# 3.net
KiCad netlist of a schematic drawn in EAGLE
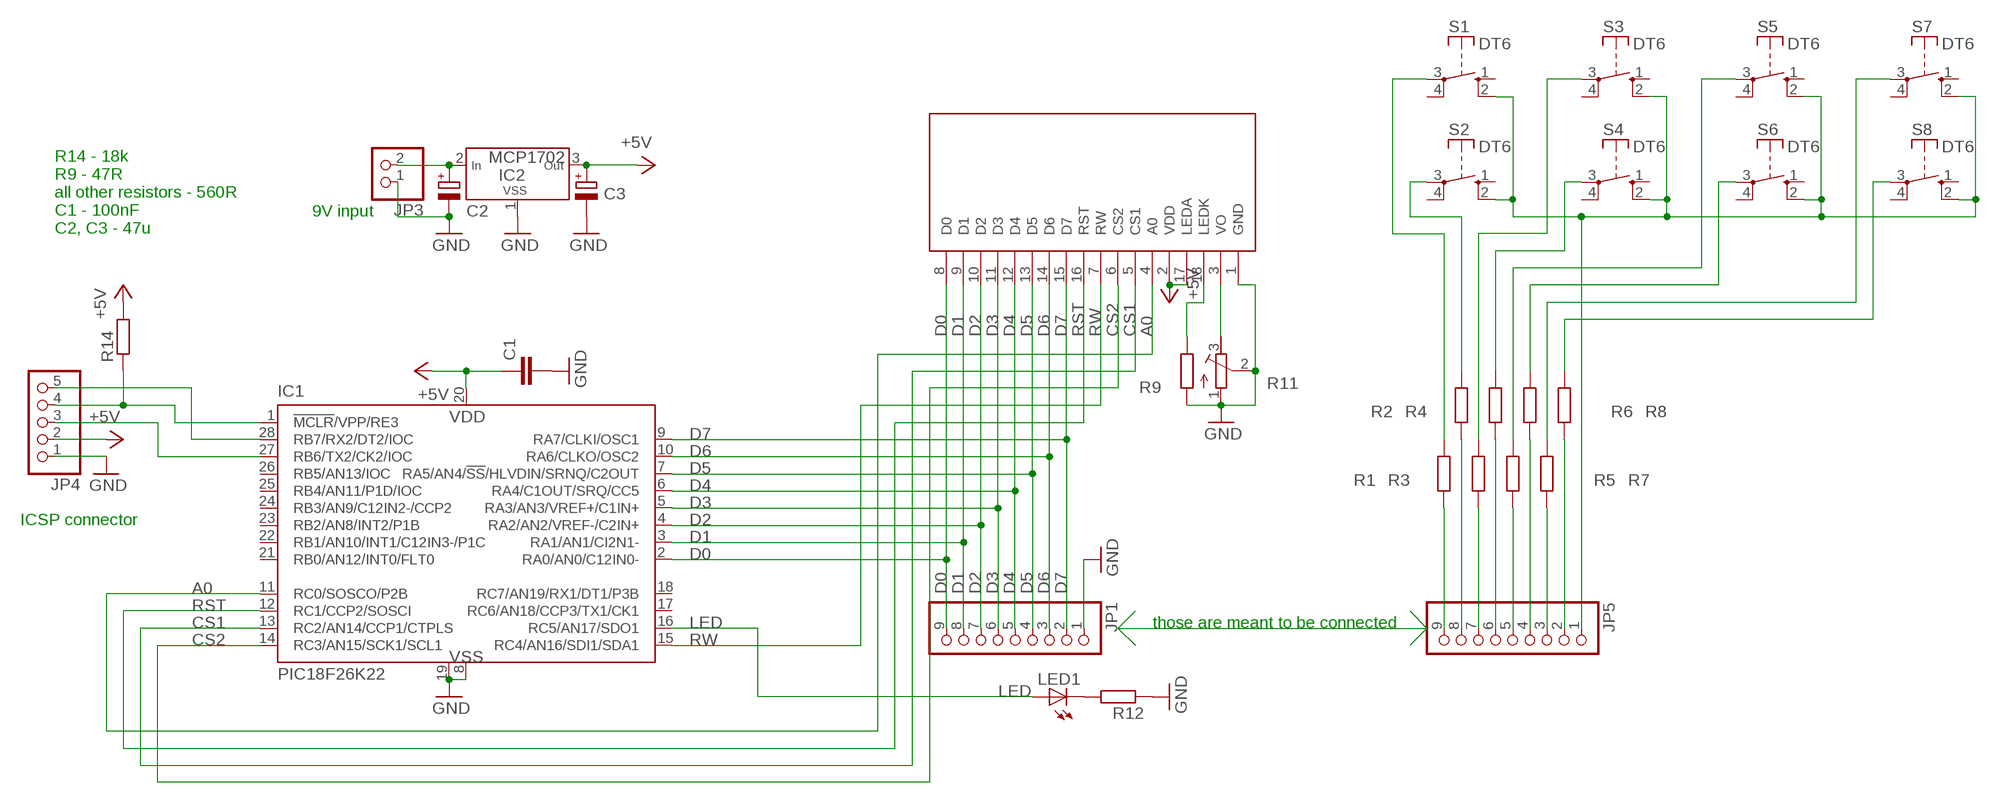
[diagram p0: schematic, sheet 1]

(export (version "E")
  (design (tool "Eeschema 10.0.6"))
  (components
    (comp (ref "C1")
      (value "C-EU025-025X050")
      (footprint "eagle-import:C025-025X050")
      (libsource (lib "eagle-import") (part "C-EU025-025X050"))
    )
    (comp (ref "C2")
      (value "CPOL-EUE2-4")
      (footprint "eagle-import:E2-4")
      (libsource (lib "eagle-import") (part "CPOL-EUE2-4"))
    )
    (comp (ref "C3")
      (value "CPOL-EUE2-4")
      (footprint "eagle-import:E2-4")
      (libsource (lib "eagle-import") (part "CPOL-EUE2-4"))
    )
    (comp (ref "IC1")
      (value "PIC18F26K22")
      (footprint "eagle-import:DIL28-3")
      (libsource (lib "eagle-import") (part "PIC18F26K22"))
    )
    (comp (ref "IC2")
      (value "MCP1702")
      (footprint "eagle-import:TO-92")
      (libsource (lib "eagle-import") (part "MCP1702"))
    )
    (comp (ref "JP1")
      (value "PINHD-1X09_2.54-90°")
      (footprint "eagle-import:1X09_90")
      (libsource (lib "eagle-import") (part "PINHD-1X09_2.54-90°"))
    )
    (comp (ref "JP3")
      (value "PINHD-1X2")
      (footprint "eagle-import:1X02")
      (libsource (lib "eagle-import") (part "PINHD-1X2"))
    )
    (comp (ref "JP4")
      (value "PINHD-1X05_2.54-90°")
      (footprint "eagle-import:1X05_90")
      (libsource (lib "eagle-import") (part "PINHD-1X05_2.54-90°"))
    )
    (comp (ref "JP5")
      (value "PINHD-1X09_2.54-90°")
      (footprint "eagle-import:1X09_90")
      (libsource (lib "eagle-import") (part "PINHD-1X09_2.54-90°"))
    )
    (comp (ref "LCD1")
      (value "DEM122032")
      (footprint "eagle-import:DEM122032")
      (libsource (lib "eagle-import") (part "DEM122032"))
    )
    (comp (ref "LED1")
      (value "LED3MM")
      (footprint "eagle-import:LED3MM")
      (libsource (lib "eagle-import") (part "LED3MM"))
    )
    (comp (ref "R1")
      (value "R_0207")
      (footprint "eagle-import:R_0207_BIGPADS")
      (libsource (lib "eagle-import") (part "R_0207"))
    )
    (comp (ref "R2")
      (value "R_0207")
      (footprint "eagle-import:R_0207_BIGPADS")
      (libsource (lib "eagle-import") (part "R_0207"))
    )
    (comp (ref "R3")
      (value "R_0207")
      (footprint "eagle-import:R_0207_BIGPADS")
      (libsource (lib "eagle-import") (part "R_0207"))
    )
    (comp (ref "R4")
      (value "R_0207")
      (footprint "eagle-import:R_0207_BIGPADS")
      (libsource (lib "eagle-import") (part "R_0207"))
    )
    (comp (ref "R5")
      (value "R_0207")
      (footprint "eagle-import:R_0207_BIGPADS")
      (libsource (lib "eagle-import") (part "R_0207"))
    )
    (comp (ref "R6")
      (value "R_0207")
      (footprint "eagle-import:R_0207_BIGPADS")
      (libsource (lib "eagle-import") (part "R_0207"))
    )
    (comp (ref "R7")
      (value "R_0207")
      (footprint "eagle-import:R_0207_BIGPADS")
      (libsource (lib "eagle-import") (part "R_0207"))
    )
    (comp (ref "R8")
      (value "R_0207")
      (footprint "eagle-import:R_0207_BIGPADS")
      (libsource (lib "eagle-import") (part "R_0207"))
    )
    (comp (ref "R9")
      (value "R_0207")
      (footprint "eagle-import:R_0207_BIGPADS")
      (libsource (lib "eagle-import") (part "R_0207"))
    )
    (comp (ref "R11")
      (value "R-TRIMM3339P")
      (footprint "eagle-import:RTRIM3339P")
      (libsource (lib "eagle-import") (part "R-TRIMM3339P"))
    )
    (comp (ref "R12")
      (value "R_0207")
      (footprint "eagle-import:R_0207_BIGPADS")
      (libsource (lib "eagle-import") (part "R_0207"))
    )
    (comp (ref "R14")
      (value "R_0207")
      (footprint "eagle-import:R_0207_BIGPADS")
      (libsource (lib "eagle-import") (part "R_0207"))
    )
    (comp (ref "S1")
      (value "DT6")
      (footprint "eagle-import:DT6")
      (libsource (lib "eagle-import") (part "DT6"))
    )
    (comp (ref "S2")
      (value "DT6")
      (footprint "eagle-import:DT6")
      (libsource (lib "eagle-import") (part "DT6"))
    )
    (comp (ref "S3")
      (value "DT6")
      (footprint "eagle-import:DT6")
      (libsource (lib "eagle-import") (part "DT6"))
    )
    (comp (ref "S4")
      (value "DT6")
      (footprint "eagle-import:DT6")
      (libsource (lib "eagle-import") (part "DT6"))
    )
    (comp (ref "S5")
      (value "DT6")
      (footprint "eagle-import:DT6")
      (libsource (lib "eagle-import") (part "DT6"))
    )
    (comp (ref "S6")
      (value "DT6")
      (footprint "eagle-import:DT6")
      (libsource (lib "eagle-import") (part "DT6"))
    )
    (comp (ref "S7")
      (value "DT6")
      (footprint "eagle-import:DT6")
      (libsource (lib "eagle-import") (part "DT6"))
    )
    (comp (ref "S8")
      (value "DT6")
      (footprint "eagle-import:DT6")
      (libsource (lib "eagle-import") (part "DT6"))
    )
  )
  (nets
    (net (code "1") (name "+5V") (class "Default")
      (node (ref "C1") (pin "1") (pinfunction "1_1") (pintype "passive"))
      (node (ref "C3") (pin "+") (pinfunction "+_+") (pintype "passive"))
      (node (ref "IC1") (pin "20") (pinfunction "VDD_20") (pintype "power_in"))
      (node (ref "IC2") (pin "3") (pinfunction "OUT_3") (pintype "output"))
      (node (ref "JP4") (pin "2") (pinfunction "2_2") (pintype "passive"))
      (node (ref "LCD1") (pin "17") (pinfunction "LEDA_17") (pintype "bidirectional"))
      (node (ref "LCD1") (pin "2") (pinfunction "VDD_2") (pintype "bidirectional"))
      (node (ref "R14") (pin "P$2") (pinfunction "2_P$2") (pintype "passive"))
    )
    (net (code "2") (name "/A0") (class "Default")
      (node (ref "IC1") (pin "11") (pinfunction "RC0/SOSCO/P2B_11") (pintype "bidirectional"))
      (node (ref "LCD1") (pin "4") (pinfunction "A0_4") (pintype "bidirectional"))
    )
    (net (code "3") (name "/CS1") (class "Default")
      (node (ref "IC1") (pin "13") (pinfunction "RC2/AN14/CCP1/CTPLS_13") (pintype "bidirectional"))
      (node (ref "LCD1") (pin "5") (pinfunction "CS1_5") (pintype "bidirectional"))
    )
    (net (code "4") (name "/CS2") (class "Default")
      (node (ref "IC1") (pin "14") (pinfunction "RC3/AN15/SCK1/SCL1_14") (pintype "bidirectional"))
      (node (ref "LCD1") (pin "6") (pinfunction "CS2_6") (pintype "bidirectional"))
    )
    (net (code "5") (name "/D0") (class "Default")
      (node (ref "IC1") (pin "2") (pinfunction "RA0/AN0/C12IN0-_2") (pintype "bidirectional"))
      (node (ref "JP1") (pin "9") (pinfunction "9_9") (pintype "passive"))
      (node (ref "LCD1") (pin "8") (pinfunction "D0_8") (pintype "bidirectional"))
    )
    (net (code "6") (name "/D1") (class "Default")
      (node (ref "IC1") (pin "3") (pinfunction "RA1/AN1/CI2N1-_3") (pintype "bidirectional"))
      (node (ref "JP1") (pin "8") (pinfunction "8_8") (pintype "passive"))
      (node (ref "LCD1") (pin "9") (pinfunction "D1_9") (pintype "bidirectional"))
    )
    (net (code "7") (name "/D2") (class "Default")
      (node (ref "IC1") (pin "4") (pinfunction "RA2/AN2/VREF-/C2IN+_4") (pintype "bidirectional"))
      (node (ref "JP1") (pin "7") (pinfunction "7_7") (pintype "passive"))
      (node (ref "LCD1") (pin "10") (pinfunction "D2_10") (pintype "bidirectional"))
    )
    (net (code "8") (name "/D3") (class "Default")
      (node (ref "IC1") (pin "5") (pinfunction "RA3/AN3/VREF+/C1IN+_5") (pintype "bidirectional"))
      (node (ref "JP1") (pin "6") (pinfunction "6_6") (pintype "passive"))
      (node (ref "LCD1") (pin "11") (pinfunction "D3_11") (pintype "bidirectional"))
    )
    (net (code "9") (name "/D4") (class "Default")
      (node (ref "IC1") (pin "6") (pinfunction "RA4/C1OUT/SRQ/CC5_6") (pintype "bidirectional"))
      (node (ref "JP1") (pin "5") (pinfunction "5_5") (pintype "passive"))
      (node (ref "LCD1") (pin "12") (pinfunction "D4_12") (pintype "bidirectional"))
    )
    (net (code "10") (name "/D5") (class "Default")
      (node (ref "IC1") (pin "7") (pinfunction "RA5/AN4/~{SS}/HLVDIN/SRNQ/C2OUT_7") (pintype "bidirectional"))
      (node (ref "JP1") (pin "4") (pinfunction "4_4") (pintype "passive"))
      (node (ref "LCD1") (pin "13") (pinfunction "D5_13") (pintype "bidirectional"))
    )
    (net (code "11") (name "/D6") (class "Default")
      (node (ref "IC1") (pin "10") (pinfunction "RA6/CLKO/OSC2_10") (pintype "output"))
      (node (ref "JP1") (pin "3") (pinfunction "3_3") (pintype "passive"))
      (node (ref "LCD1") (pin "14") (pinfunction "D6_14") (pintype "bidirectional"))
    )
    (net (code "12") (name "/D7") (class "Default")
      (node (ref "IC1") (pin "9") (pinfunction "RA7/CLKI/OSC1_9") (pintype "input"))
      (node (ref "JP1") (pin "2") (pinfunction "2_2") (pintype "passive"))
      (node (ref "LCD1") (pin "15") (pinfunction "D7_15") (pintype "bidirectional"))
    )
    (net (code "13") (name "/LED") (class "Default")
      (node (ref "IC1") (pin "16") (pinfunction "RC5/AN17/SDO1_16") (pintype "bidirectional"))
      (node (ref "LED1") (pin "A") (pinfunction "A_A") (pintype "passive"))
    )
    (net (code "14") (name "/RST") (class "Default")
      (node (ref "IC1") (pin "12") (pinfunction "RC1/CCP2/SOSCI_12") (pintype "bidirectional"))
      (node (ref "LCD1") (pin "16") (pinfunction "RST_16") (pintype "bidirectional"))
    )
    (net (code "15") (name "/RW") (class "Default")
      (node (ref "IC1") (pin "15") (pinfunction "RC4/AN16/SDI1/SDA1_15") (pintype "bidirectional"))
      (node (ref "LCD1") (pin "7") (pinfunction "RW_7") (pintype "bidirectional"))
    )
    (net (code "16") (name "GND") (class "Default")
      (node (ref "C1") (pin "2") (pinfunction "2_2") (pintype "passive"))
      (node (ref "C2") (pin "-") (pinfunction "-_-") (pintype "passive"))
      (node (ref "C3") (pin "-") (pinfunction "-_-") (pintype "passive"))
      (node (ref "IC1") (pin "19") (pinfunction "VSS_19") (pintype "power_in"))
      (node (ref "IC1") (pin "8") (pinfunction "VSS_8") (pintype "power_in"))
      (node (ref "IC2") (pin "1") (pinfunction "VSS_1") (pintype "input"))
      (node (ref "JP1") (pin "1") (pinfunction "1_1") (pintype "passive"))
      (node (ref "JP3") (pin "1") (pinfunction "1_1") (pintype "passive"))
      (node (ref "JP4") (pin "1") (pinfunction "1_1") (pintype "passive"))
      (node (ref "LCD1") (pin "1") (pinfunction "GND_1") (pintype "bidirectional"))
      (node (ref "R11") (pin "1") (pinfunction "E_1") (pintype "passive"))
      (node (ref "R11") (pin "2") (pinfunction "S_2") (pintype "passive"))
      (node (ref "R12") (pin "P$1") (pinfunction "1_P$1") (pintype "passive"))
      (node (ref "R9") (pin "P$1") (pinfunction "1_P$1") (pintype "passive"))
    )
    (net (code "17") (name "Net-(IC1-RB6{slash}TX2{slash}CK2{slash}IOC)") (class "Default")
      (node (ref "IC1") (pin "27") (pinfunction "RB6/TX2/CK2/IOC_27") (pintype "bidirectional"))
      (node (ref "JP4") (pin "3") (pinfunction "3_3") (pintype "passive"))
    )
    (net (code "18") (name "Net-(IC1-RB7{slash}RX2{slash}DT2{slash}IOC)") (class "Default")
      (node (ref "IC1") (pin "28") (pinfunction "RB7/RX2/DT2/IOC_28") (pintype "bidirectional"))
      (node (ref "JP4") (pin "5") (pinfunction "5_5") (pintype "passive"))
    )
    (net (code "19") (name "Net-(IC1-~{MCLR}{slash}VPP{slash}RE3)") (class "Default")
      (node (ref "IC1") (pin "1") (pinfunction "~{MCLR}/VPP/RE3_1") (pintype "input"))
      (node (ref "JP4") (pin "4") (pinfunction "4_4") (pintype "passive"))
      (node (ref "R14") (pin "P$1") (pinfunction "1_P$1") (pintype "passive"))
    )
    (net (code "20") (name "Net-(IC2-IN)") (class "Default")
      (node (ref "C2") (pin "+") (pinfunction "+_+") (pintype "passive"))
      (node (ref "IC2") (pin "2") (pinfunction "IN_2") (pintype "input"))
      (node (ref "JP3") (pin "2") (pinfunction "2_2") (pintype "passive"))
    )
    (net (code "21") (name "Net-(JP5-Pad1)") (class "Default")
      (node (ref "JP5") (pin "1") (pinfunction "1_1") (pintype "passive"))
      (node (ref "S1") (pin "2") (pinfunction "S_2") (pintype "passive"))
      (node (ref "S2") (pin "2") (pinfunction "S_2") (pintype "passive"))
      (node (ref "S3") (pin "2") (pinfunction "S_2") (pintype "passive"))
      (node (ref "S4") (pin "2") (pinfunction "S_2") (pintype "passive"))
      (node (ref "S5") (pin "2") (pinfunction "S_2") (pintype "passive"))
      (node (ref "S6") (pin "2") (pinfunction "S_2") (pintype "passive"))
      (node (ref "S7") (pin "2") (pinfunction "S_2") (pintype "passive"))
      (node (ref "S8") (pin "2") (pinfunction "S_2") (pintype "passive"))
    )
    (net (code "22") (name "Net-(LCD1-LEDK)") (class "Default")
      (node (ref "LCD1") (pin "18") (pinfunction "LEDK_18") (pintype "bidirectional"))
      (node (ref "R9") (pin "P$2") (pinfunction "2_P$2") (pintype "passive"))
    )
    (net (code "23") (name "Net-(LCD1-VO)") (class "Default")
      (node (ref "LCD1") (pin "3") (pinfunction "VO_3") (pintype "bidirectional"))
      (node (ref "R11") (pin "3") (pinfunction "A_3") (pintype "passive"))
    )
    (net (code "24") (name "Net-(LED1-C)") (class "Default")
      (node (ref "LED1") (pin "K") (pinfunction "C_K") (pintype "passive"))
      (node (ref "R12") (pin "P$2") (pinfunction "2_P$2") (pintype "passive"))
    )
    (net (code "25") (name "Net-(R1-1)") (class "Default")
      (node (ref "JP5") (pin "9") (pinfunction "9_9") (pintype "passive"))
      (node (ref "R1") (pin "P$1") (pinfunction "1_P$1") (pintype "passive"))
    )
    (net (code "26") (name "Net-(R1-2)") (class "Default")
      (node (ref "R1") (pin "P$2") (pinfunction "2_P$2") (pintype "passive"))
      (node (ref "S1") (pin "3") (pinfunction "P_3") (pintype "passive"))
    )
    (net (code "27") (name "Net-(R2-1)") (class "Default")
      (node (ref "JP5") (pin "8") (pinfunction "8_8") (pintype "passive"))
      (node (ref "R2") (pin "P$1") (pinfunction "1_P$1") (pintype "passive"))
    )
    (net (code "28") (name "Net-(R2-2)") (class "Default")
      (node (ref "R2") (pin "P$2") (pinfunction "2_P$2") (pintype "passive"))
      (node (ref "S2") (pin "3") (pinfunction "P_3") (pintype "passive"))
    )
    (net (code "29") (name "Net-(R3-1)") (class "Default")
      (node (ref "JP5") (pin "7") (pinfunction "7_7") (pintype "passive"))
      (node (ref "R3") (pin "P$1") (pinfunction "1_P$1") (pintype "passive"))
    )
    (net (code "30") (name "Net-(R3-2)") (class "Default")
      (node (ref "R3") (pin "P$2") (pinfunction "2_P$2") (pintype "passive"))
      (node (ref "S3") (pin "3") (pinfunction "P_3") (pintype "passive"))
    )
    (net (code "31") (name "Net-(R4-1)") (class "Default")
      (node (ref "JP5") (pin "6") (pinfunction "6_6") (pintype "passive"))
      (node (ref "R4") (pin "P$1") (pinfunction "1_P$1") (pintype "passive"))
    )
    (net (code "32") (name "Net-(R4-2)") (class "Default")
      (node (ref "R4") (pin "P$2") (pinfunction "2_P$2") (pintype "passive"))
      (node (ref "S4") (pin "3") (pinfunction "P_3") (pintype "passive"))
    )
    (net (code "33") (name "Net-(R5-1)") (class "Default")
      (node (ref "JP5") (pin "5") (pinfunction "5_5") (pintype "passive"))
      (node (ref "R5") (pin "P$1") (pinfunction "1_P$1") (pintype "passive"))
    )
    (net (code "34") (name "Net-(R5-2)") (class "Default")
      (node (ref "R5") (pin "P$2") (pinfunction "2_P$2") (pintype "passive"))
      (node (ref "S5") (pin "3") (pinfunction "P_3") (pintype "passive"))
    )
    (net (code "35") (name "Net-(R6-1)") (class "Default")
      (node (ref "JP5") (pin "4") (pinfunction "4_4") (pintype "passive"))
      (node (ref "R6") (pin "P$1") (pinfunction "1_P$1") (pintype "passive"))
    )
    (net (code "36") (name "Net-(R6-2)") (class "Default")
      (node (ref "R6") (pin "P$2") (pinfunction "2_P$2") (pintype "passive"))
      (node (ref "S6") (pin "3") (pinfunction "P_3") (pintype "passive"))
    )
    (net (code "37") (name "Net-(R7-1)") (class "Default")
      (node (ref "JP5") (pin "3") (pinfunction "3_3") (pintype "passive"))
      (node (ref "R7") (pin "P$1") (pinfunction "1_P$1") (pintype "passive"))
    )
    (net (code "38") (name "Net-(R7-2)") (class "Default")
      (node (ref "R7") (pin "P$2") (pinfunction "2_P$2") (pintype "passive"))
      (node (ref "S7") (pin "3") (pinfunction "P_3") (pintype "passive"))
    )
    (net (code "39") (name "Net-(R8-1)") (class "Default")
      (node (ref "JP5") (pin "2") (pinfunction "2_2") (pintype "passive"))
      (node (ref "R8") (pin "P$1") (pinfunction "1_P$1") (pintype "passive"))
    )
    (net (code "40") (name "Net-(R8-2)") (class "Default")
      (node (ref "R8") (pin "P$2") (pinfunction "2_P$2") (pintype "passive"))
      (node (ref "S8") (pin "3") (pinfunction "P_3") (pintype "passive"))
    )
    (net (code "41") (name "unconnected-(IC1-RB0{slash}AN12{slash}INT0{slash}FLT0-Pad21)") (class "Default")
      (node (ref "IC1") (pin "21") (pinfunction "RB0/AN12/INT0/FLT0_21") (pintype "bidirectional"))
    )
    (net (code "42") (name "unconnected-(IC1-RB1{slash}AN10{slash}INT1{slash}C12IN3-{slash}P1C-Pad22)") (class "Default")
      (node (ref "IC1") (pin "22") (pinfunction "RB1/AN10/INT1/C12IN3-/P1C_22") (pintype "bidirectional"))
    )
    (net (code "43") (name "unconnected-(IC1-RB2{slash}AN8{slash}INT2{slash}P1B-Pad23)") (class "Default")
      (node (ref "IC1") (pin "23") (pinfunction "RB2/AN8/INT2/P1B_23") (pintype "bidirectional"))
    )
    (net (code "44") (name "unconnected-(IC1-RB3{slash}AN9{slash}C12IN2-{slash}CCP2-Pad24)") (class "Default")
      (node (ref "IC1") (pin "24") (pinfunction "RB3/AN9/C12IN2-/CCP2_24") (pintype "bidirectional"))
    )
    (net (code "45") (name "unconnected-(IC1-RB4{slash}AN11{slash}P1D{slash}IOC-Pad25)") (class "Default")
      (node (ref "IC1") (pin "25") (pinfunction "RB4/AN11/P1D/IOC_25") (pintype "bidirectional"))
    )
    (net (code "46") (name "unconnected-(IC1-RB5{slash}AN13{slash}IOC-Pad26)") (class "Default")
      (node (ref "IC1") (pin "26") (pinfunction "RB5/AN13/IOC_26") (pintype "bidirectional"))
    )
    (net (code "47") (name "unconnected-(IC1-RC6{slash}AN18{slash}CCP3{slash}TX1{slash}CK1-Pad17)") (class "Default")
      (node (ref "IC1") (pin "17") (pinfunction "RC6/AN18/CCP3/TX1/CK1_17") (pintype "bidirectional"))
    )
    (net (code "48") (name "unconnected-(IC1-RC7{slash}AN19{slash}RX1{slash}DT1{slash}P3B-Pad18)") (class "Default")
      (node (ref "IC1") (pin "18") (pinfunction "RC7/AN19/RX1/DT1/P3B_18") (pintype "bidirectional"))
    )
    (net (code "49") (name "unconnected-(S1-P-Pad4)") (class "Default")
      (node (ref "S1") (pin "4") (pinfunction "P_4") (pintype "passive"))
    )
    (net (code "50") (name "unconnected-(S1-S-Pad1)") (class "Default")
      (node (ref "S1") (pin "1") (pinfunction "S_1") (pintype "passive"))
    )
    (net (code "51") (name "unconnected-(S2-P-Pad4)") (class "Default")
      (node (ref "S2") (pin "4") (pinfunction "P_4") (pintype "passive"))
    )
    (net (code "52") (name "unconnected-(S2-S-Pad1)") (class "Default")
      (node (ref "S2") (pin "1") (pinfunction "S_1") (pintype "passive"))
    )
    (net (code "53") (name "unconnected-(S3-P-Pad4)") (class "Default")
      (node (ref "S3") (pin "4") (pinfunction "P_4") (pintype "passive"))
    )
    (net (code "54") (name "unconnected-(S3-S-Pad1)") (class "Default")
      (node (ref "S3") (pin "1") (pinfunction "S_1") (pintype "passive"))
    )
    (net (code "55") (name "unconnected-(S4-P-Pad4)") (class "Default")
      (node (ref "S4") (pin "4") (pinfunction "P_4") (pintype "passive"))
    )
    (net (code "56") (name "unconnected-(S4-S-Pad1)") (class "Default")
      (node (ref "S4") (pin "1") (pinfunction "S_1") (pintype "passive"))
    )
    (net (code "57") (name "unconnected-(S5-P-Pad4)") (class "Default")
      (node (ref "S5") (pin "4") (pinfunction "P_4") (pintype "passive"))
    )
    (net (code "58") (name "unconnected-(S5-S-Pad1)") (class "Default")
      (node (ref "S5") (pin "1") (pinfunction "S_1") (pintype "passive"))
    )
    (net (code "59") (name "unconnected-(S6-P-Pad4)") (class "Default")
      (node (ref "S6") (pin "4") (pinfunction "P_4") (pintype "passive"))
    )
    (net (code "60") (name "unconnected-(S6-S-Pad1)") (class "Default")
      (node (ref "S6") (pin "1") (pinfunction "S_1") (pintype "passive"))
    )
    (net (code "61") (name "unconnected-(S7-P-Pad4)") (class "Default")
      (node (ref "S7") (pin "4") (pinfunction "P_4") (pintype "passive"))
    )
    (net (code "62") (name "unconnected-(S7-S-Pad1)") (class "Default")
      (node (ref "S7") (pin "1") (pinfunction "S_1") (pintype "passive"))
    )
    (net (code "63") (name "unconnected-(S8-P-Pad4)") (class "Default")
      (node (ref "S8") (pin "4") (pinfunction "P_4") (pintype "passive"))
    )
    (net (code "64") (name "unconnected-(S8-S-Pad1)") (class "Default")
      (node (ref "S8") (pin "1") (pinfunction "S_1") (pintype "passive"))
    )
  )
)
